# ProPrj___2025-09-13.net
KiCad netlist of a schematic drawn in EasyEDA Pro
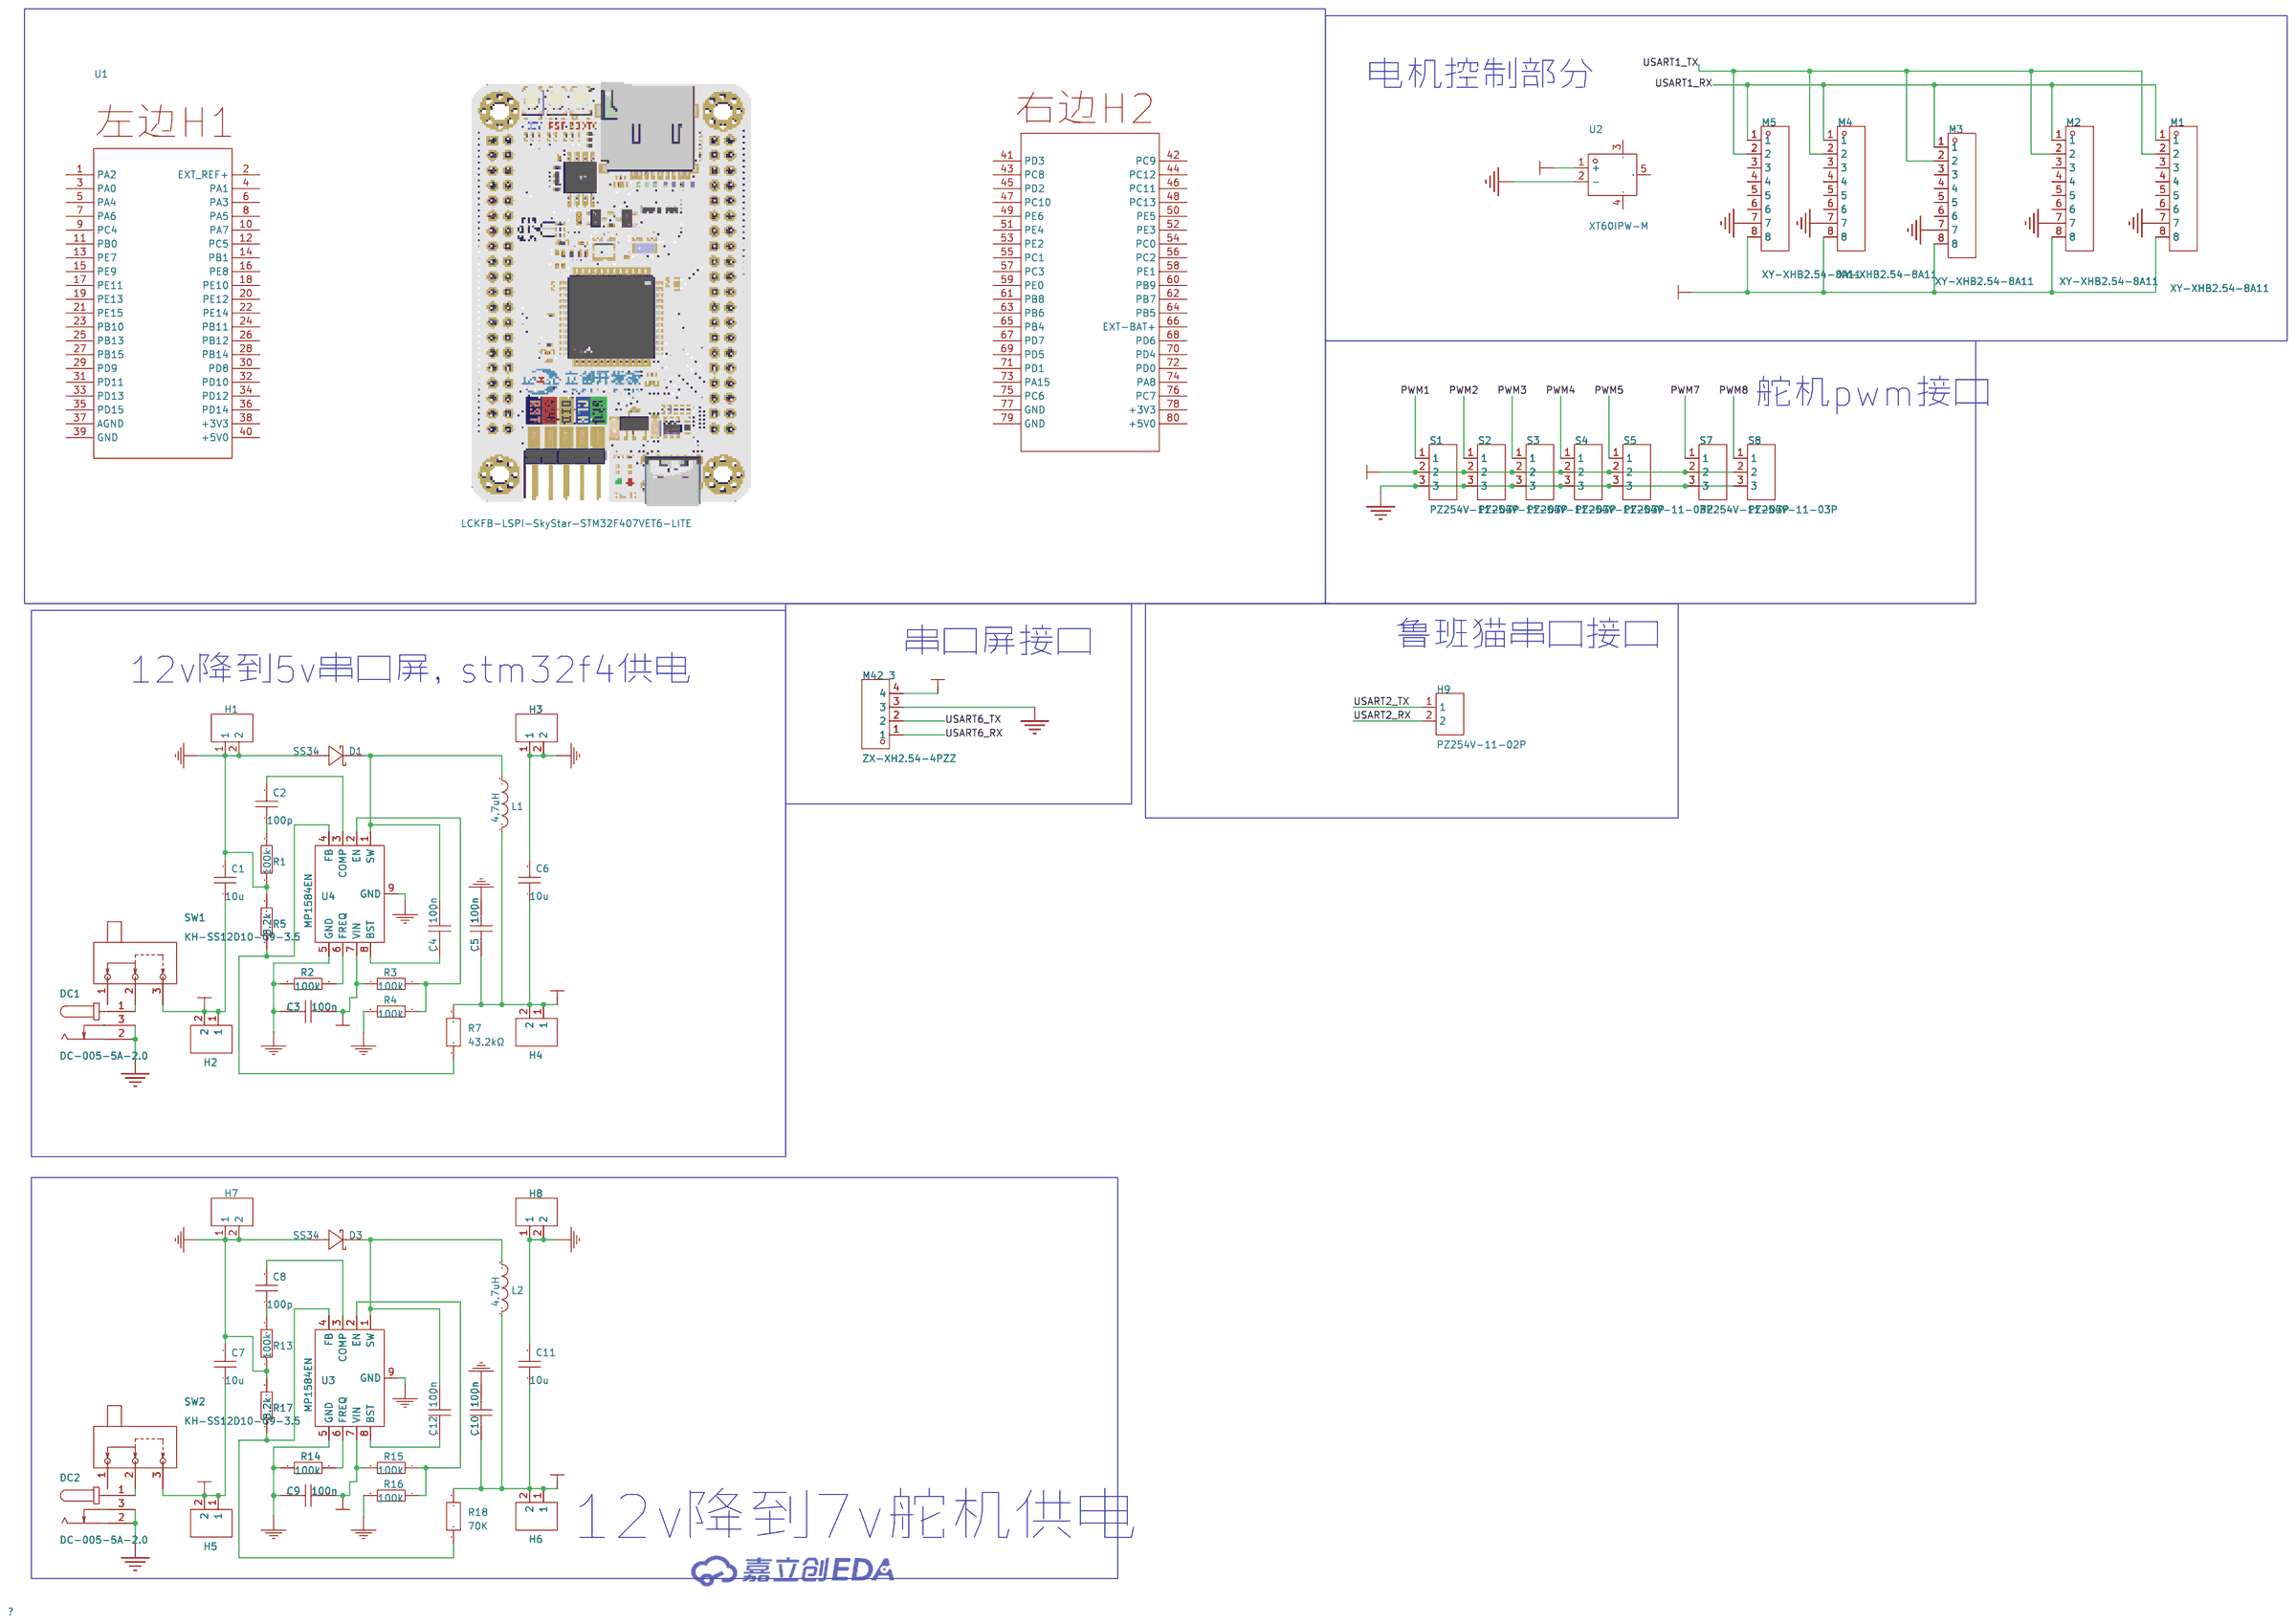
[diagram p0: schematic sheet]

(export (version "E")
  (design (tool "Eeschema 10.0.6"))
  (components
    (comp (ref "C1")
      (value "10u")
      (footprint "easyedapro:C1206")
      (fields (field (name "Manufacturer Part") "CL31A106KBHNNNE") (field (name "Manufacturer") "SAMSUNG"))
      (libsource (lib "easyedapro") (part "10u"))
    )
    (comp (ref "C2")
      (value "100p")
      (footprint "easyedapro:C0603")
      (fields (field (name "Manufacturer Part") "0603CG101J500NT") (field (name "Manufacturer") "FH"))
      (libsource (lib "easyedapro") (part "100p"))
    )
    (comp (ref "C3")
      (value "100n")
      (footprint "easyedapro:C0603")
      (fields (field (name "Manufacturer Part") "CC0603KRX7R9BB104") (field (name "Manufacturer") "YAGEO"))
      (libsource (lib "easyedapro") (part "100n"))
    )
    (comp (ref "C4")
      (value "100n")
      (footprint "easyedapro:C0603")
      (fields (field (name "Manufacturer Part") "CC0603KRX7R9BB104") (field (name "Manufacturer") "YAGEO"))
      (libsource (lib "easyedapro") (part "100n"))
    )
    (comp (ref "C5")
      (value "100n")
      (footprint "easyedapro:C0603")
      (fields (field (name "Manufacturer Part") "CC0603KRX7R9BB104") (field (name "Manufacturer") "YAGEO"))
      (libsource (lib "easyedapro") (part "100n"))
    )
    (comp (ref "C6")
      (value "10u")
      (footprint "easyedapro:C1206")
      (fields (field (name "Manufacturer Part") "CL31A106KBHNNNE") (field (name "Manufacturer") "SAMSUNG"))
      (libsource (lib "easyedapro") (part "10u"))
    )
    (comp (ref "C7")
      (value "10u")
      (footprint "easyedapro:C1206")
      (fields (field (name "Manufacturer Part") "CL31A106KBHNNNE") (field (name "Manufacturer") "SAMSUNG"))
      (libsource (lib "easyedapro") (part "10u"))
    )
    (comp (ref "C8")
      (value "100p")
      (footprint "easyedapro:C0603")
      (fields (field (name "Manufacturer Part") "0603CG101J500NT") (field (name "Manufacturer") "FH"))
      (libsource (lib "easyedapro") (part "100p"))
    )
    (comp (ref "C9")
      (value "100n")
      (footprint "easyedapro:C0603")
      (fields (field (name "Manufacturer Part") "CC0603KRX7R9BB104") (field (name "Manufacturer") "YAGEO"))
      (libsource (lib "easyedapro") (part "100n"))
    )
    (comp (ref "C10")
      (value "100n")
      (footprint "easyedapro:C0603")
      (fields (field (name "Manufacturer Part") "CC0603KRX7R9BB104") (field (name "Manufacturer") "YAGEO"))
      (libsource (lib "easyedapro") (part "100n"))
    )
    (comp (ref "C11")
      (value "10u")
      (footprint "easyedapro:C1206")
      (fields (field (name "Manufacturer Part") "CL31A106KBHNNNE") (field (name "Manufacturer") "SAMSUNG"))
      (libsource (lib "easyedapro") (part "10u"))
    )
    (comp (ref "C12")
      (value "100n")
      (footprint "easyedapro:C0603")
      (fields (field (name "Manufacturer Part") "CC0603KRX7R9BB104") (field (name "Manufacturer") "YAGEO"))
      (libsource (lib "easyedapro") (part "100n"))
    )
    (comp (ref "D1")
      (value "SS34")
      (footprint "easyedapro:SMA_L4.2-W2.7-LS5.0-RD")
      (fields (field (name "Manufacturer") "KUU"))
      (libsource (lib "easyedapro") (part "SS34"))
    )
    (comp (ref "D3")
      (value "SS34")
      (footprint "easyedapro:SMA_L4.2-W2.7-LS5.0-RD")
      (fields (field (name "Manufacturer") "KUU"))
      (libsource (lib "easyedapro") (part "SS34"))
    )
    (comp (ref "DC1")
      (value "DC-005-5A-2.0")
      (footprint "easyedapro:DC-IN-TH_DC-005-5A-2.0")
      (description "连接器类型:DC电源插座;安装方式:弯插;触点内径:2mm;触点外径:6.2mm;额定电流:5A;额定电压:24V;工作温度范围:-20°C~+70°C;")
      (fields (field (name "Manufacturer") "XKB Connection(中国星坤)"))
      (libsource (lib "easyedapro") (part "DC-005-5A-2.0"))
    )
    (comp (ref "DC2")
      (value "DC-005-5A-2.0")
      (footprint "easyedapro:DC-IN-TH_DC-005-5A-2.0")
      (description "连接器类型:DC电源插座;安装方式:弯插;触点内径:2mm;触点外径:6.2mm;额定电流:5A;额定电压:24V;工作温度范围:-20°C~+70°C;")
      (fields (field (name "Manufacturer") "XKB Connection(中国星坤)"))
      (libsource (lib "easyedapro") (part "DC-005-5A-2.0"))
    )
    (comp (ref "H1")
      (value "KH-2.54PH180-1X2P-L11.5")
      (footprint "easyedapro:HDR-TH_2P-P2.54-V-M")
      (fields (field (name "Manufacturer") "kinghelm(金航标)"))
      (libsource (lib "easyedapro") (part "KH-2.54PH180-1X2P-L11.5"))
    )
    (comp (ref "H2")
      (value "KH-2.54PH180-1X2P-L11.5")
      (footprint "easyedapro:HDR-TH_2P-P2.54-V-M")
      (fields (field (name "Manufacturer") "kinghelm(金航标)"))
      (libsource (lib "easyedapro") (part "KH-2.54PH180-1X2P-L11.5"))
    )
    (comp (ref "H3")
      (value "KH-2.54PH180-1X2P-L11.5")
      (footprint "easyedapro:HDR-TH_2P-P2.54-V-M")
      (fields (field (name "Manufacturer") "kinghelm(金航标)"))
      (libsource (lib "easyedapro") (part "KH-2.54PH180-1X2P-L11.5"))
    )
    (comp (ref "H4")
      (value "KH-2.54PH180-1X2P-L11.5")
      (footprint "easyedapro:HDR-TH_2P-P2.54-V-M")
      (fields (field (name "Manufacturer") "kinghelm(金航标)"))
      (libsource (lib "easyedapro") (part "KH-2.54PH180-1X2P-L11.5"))
    )
    (comp (ref "H5")
      (value "KH-2.54PH180-1X2P-L11.5")
      (footprint "easyedapro:HDR-TH_2P-P2.54-V-M")
      (fields (field (name "Manufacturer") "kinghelm(金航标)"))
      (libsource (lib "easyedapro") (part "KH-2.54PH180-1X2P-L11.5"))
    )
    (comp (ref "H6")
      (value "KH-2.54PH180-1X2P-L11.5")
      (footprint "easyedapro:HDR-TH_2P-P2.54-V-M")
      (fields (field (name "Manufacturer") "kinghelm(金航标)"))
      (libsource (lib "easyedapro") (part "KH-2.54PH180-1X2P-L11.5"))
    )
    (comp (ref "H7")
      (value "KH-2.54PH180-1X2P-L11.5")
      (footprint "easyedapro:HDR-TH_2P-P2.54-V-M")
      (fields (field (name "Manufacturer") "kinghelm(金航标)"))
      (libsource (lib "easyedapro") (part "KH-2.54PH180-1X2P-L11.5"))
    )
    (comp (ref "H8")
      (value "KH-2.54PH180-1X2P-L11.5")
      (footprint "easyedapro:HDR-TH_2P-P2.54-V-M")
      (fields (field (name "Manufacturer") "kinghelm(金航标)"))
      (libsource (lib "easyedapro") (part "KH-2.54PH180-1X2P-L11.5"))
    )
    (comp (ref "H9")
      (value "PZ254V-11-02P")
      (footprint "easyedapro:HDR-TH_2P-P2.54-V-M")
      (fields (field (name "Manufacturer") "XFCN(兴飞)"))
      (libsource (lib "easyedapro") (part "PZ254V-11-02P"))
    )
    (comp (ref "L1")
      (value "4.7uH")
      (footprint "easyedapro:IND-SMD_L6.0-W6.0_SLF6028T")
      (fields
        (field (name "Manufacturer Part") "SLO0630H4R7MTT")
        (field (name "Manufacturer") "Sunltech Tech")
      )
      (libsource (lib "easyedapro") (part "4.7uH"))
    )
    (comp (ref "L2")
      (value "4.7uH")
      (footprint "easyedapro:IND-SMD_L6.0-W6.0_SLF6028T")
      (fields
        (field (name "Manufacturer Part") "SLO0630H4R7MTT")
        (field (name "Manufacturer") "Sunltech Tech")
      )
      (libsource (lib "easyedapro") (part "4.7uH"))
    )
    (comp (ref "M1")
      (value "XY-XHB2.54-8A11")
      (fields (field (name "Manufacturer") "XYECONN(辛译)"))
      (libsource (lib "easyedapro") (part "KH-A2504-R-08AWD"))
    )
    (comp (ref "M2")
      (value "XY-XHB2.54-8A11")
      (fields (field (name "Manufacturer") "XYECONN(辛译)"))
      (libsource (lib "easyedapro") (part "KH-A2504-R-08AWD"))
    )
    (comp (ref "M3")
      (value "XY-XHB2.54-8A11")
      (fields (field (name "Manufacturer") "XYECONN(辛译)"))
      (libsource (lib "easyedapro") (part "KH-A2504-R-08AWD"))
    )
    (comp (ref "M4")
      (value "XY-XHB2.54-8A11")
      (fields (field (name "Manufacturer") "XYECONN(辛译)"))
      (libsource (lib "easyedapro") (part "KH-A2504-R-08AWD"))
    )
    (comp (ref "M5")
      (value "XY-XHB2.54-8A11")
      (fields (field (name "Manufacturer") "XYECONN(辛译)"))
      (libsource (lib "easyedapro") (part "KH-A2504-R-08AWD"))
    )
    (comp (ref "M42_3")
      (value "ZX-XH2.54-4PZZ")
      (footprint "easyedapro:CONN-TH_4P-P2.50_4PIN")
      (fields (field (name "Manufacturer") "Megastar(兆星)"))
      (libsource (lib "easyedapro") (part "ZX-XH2.54-4PZZ"))
    )
    (comp (ref "R1")
      (value "100k")
      (footprint "easyedapro:R0603")
      (fields (field (name "Manufacturer Part") "0603WAF1003T5E") (field (name "Manufacturer") "UniOhm"))
      (libsource (lib "easyedapro") (part "100k"))
    )
    (comp (ref "R2")
      (value "100k")
      (footprint "easyedapro:R0603")
      (fields (field (name "Manufacturer Part") "0603WAF1003T5E") (field (name "Manufacturer") "UniOhm"))
      (libsource (lib "easyedapro") (part "100k"))
    )
    (comp (ref "R3")
      (value "100k")
      (footprint "easyedapro:R0603")
      (fields (field (name "Manufacturer Part") "0603WAF1003T5E") (field (name "Manufacturer") "UniOhm"))
      (libsource (lib "easyedapro") (part "100k"))
    )
    (comp (ref "R4")
      (value "100k")
      (footprint "easyedapro:R0603")
      (fields (field (name "Manufacturer Part") "0603WAF1003T5E") (field (name "Manufacturer") "UniOhm"))
      (libsource (lib "easyedapro") (part "100k"))
    )
    (comp (ref "R5")
      (value "8.2k")
      (footprint "easyedapro:R0603")
      (fields (field (name "Manufacturer Part") "0603WAF8201T5E") (field (name "Manufacturer") "UniOhm"))
      (libsource (lib "easyedapro") (part "8.2k"))
    )
    (comp (ref "R7")
      (value "43.2kΩ")
      (footprint "easyedapro:R0603")
      (description "5V_1")
      (fields (field (name "Manufacturer Part") "FRC0603F4322TS") (field (name "Manufacturer") "FOJAN(富捷)"))
      (libsource (lib "easyedapro") (part "FRC0603F4322TS"))
    )
    (comp (ref "R13")
      (value "100k")
      (footprint "easyedapro:R0603")
      (fields (field (name "Manufacturer Part") "0603WAF1003T5E") (field (name "Manufacturer") "UniOhm"))
      (libsource (lib "easyedapro") (part "100k"))
    )
    (comp (ref "R14")
      (value "100k")
      (footprint "easyedapro:R0603")
      (fields (field (name "Manufacturer Part") "0603WAF1003T5E") (field (name "Manufacturer") "UniOhm"))
      (libsource (lib "easyedapro") (part "100k"))
    )
    (comp (ref "R15")
      (value "100k")
      (footprint "easyedapro:R0603")
      (fields (field (name "Manufacturer Part") "0603WAF1003T5E") (field (name "Manufacturer") "UniOhm"))
      (libsource (lib "easyedapro") (part "100k"))
    )
    (comp (ref "R16")
      (value "100k")
      (footprint "easyedapro:R0603")
      (fields (field (name "Manufacturer Part") "0603WAF1003T5E") (field (name "Manufacturer") "UniOhm"))
      (libsource (lib "easyedapro") (part "100k"))
    )
    (comp (ref "R17")
      (value "8.2k")
      (footprint "easyedapro:R0603")
      (fields (field (name "Manufacturer Part") "0603WAF8201T5E") (field (name "Manufacturer") "UniOhm"))
      (libsource (lib "easyedapro") (part "8.2k"))
    )
    (comp (ref "R18")
      (value "70K")
      (footprint "easyedapro:R0603")
      (description "5V_1")
      (fields (field (name "Manufacturer Part") "FRC0603F4322TS") (field (name "Manufacturer") "FOJAN(富捷)"))
      (libsource (lib "easyedapro") (part "FRC0603F4322TS"))
    )
    (comp (ref "S1")
      (value "PZ254V-11-03P")
      (footprint "easyedapro:HDR-TH_3P-P2.54-V-M")
      (fields (field (name "Manufacturer") "XFCN(兴飞)"))
      (libsource (lib "easyedapro") (part "PZ254V-11-03P_C2937625"))
    )
    (comp (ref "S2")
      (value "PZ254V-11-03P")
      (footprint "easyedapro:HDR-TH_3P-P2.54-V-M")
      (fields (field (name "Manufacturer") "XFCN(兴飞)"))
      (libsource (lib "easyedapro") (part "PZ254V-11-03P_C2937625"))
    )
    (comp (ref "S3")
      (value "PZ254V-11-03P")
      (footprint "easyedapro:HDR-TH_3P-P2.54-V-M")
      (fields (field (name "Manufacturer") "XFCN(兴飞)"))
      (libsource (lib "easyedapro") (part "PZ254V-11-03P_C2937625"))
    )
    (comp (ref "S4")
      (value "PZ254V-11-03P")
      (footprint "easyedapro:HDR-TH_3P-P2.54-V-M")
      (fields (field (name "Manufacturer") "XFCN(兴飞)"))
      (libsource (lib "easyedapro") (part "PZ254V-11-03P_C2937625"))
    )
    (comp (ref "S5")
      (value "PZ254V-11-03P")
      (footprint "easyedapro:HDR-TH_3P-P2.54-V-M")
      (fields (field (name "Manufacturer") "XFCN(兴飞)"))
      (libsource (lib "easyedapro") (part "PZ254V-11-03P_C2937625"))
    )
    (comp (ref "S7")
      (value "PZ254V-11-03P")
      (footprint "easyedapro:HDR-TH_3P-P2.54-V-M")
      (fields (field (name "Manufacturer") "XFCN(兴飞)"))
      (libsource (lib "easyedapro") (part "PZ254V-11-03P_C2937625"))
    )
    (comp (ref "S8")
      (value "PZ254V-11-03P")
      (footprint "easyedapro:HDR-TH_3P-P2.54-V-M")
      (fields (field (name "Manufacturer") "XFCN(兴飞)"))
      (libsource (lib "easyedapro") (part "PZ254V-11-03P_C2937625"))
    )
    (comp (ref "SW1")
      (value "KH-SS12D10-G9-3.5")
      (footprint "easyedapro:SW-TH_KH-SS12D10-G9-3.5")
      (fields (field (name "Manufacturer") "kinghelm(金航标)"))
      (libsource (lib "easyedapro") (part "KH-SS12D10-G9-3.5"))
    )
    (comp (ref "SW2")
      (value "KH-SS12D10-G9-3.5")
      (footprint "easyedapro:SW-TH_KH-SS12D10-G9-3.5")
      (fields (field (name "Manufacturer") "kinghelm(金航标)"))
      (libsource (lib "easyedapro") (part "KH-SS12D10-G9-3.5"))
    )
    (comp (ref "U1")
      (value "LCKFB-LSPI-SkyStar-STM32F407VET6-LITE")
      (footprint "easyedapro:COMM-TH_LCKFB-LSPI-SKYSTAR-STM32F407VET6-LITE")
      (fields (field (name "Manufacturer") "立创开发板"))
      (libsource (lib "easyedapro") (part "LCKFB-LSPI-SKYSTAR-STM32F407VET6-LITE"))
    )
    (comp (ref "U2")
      (value "XT60IPW-M")
      (footprint "easyedapro:XT60-TH_XT60IPW-M")
      (libsource (lib "easyedapro") (part "XT60IPW-M"))
    )
    (comp (ref "U3")
      (value "MP1584EN")
      (footprint "easyedapro:SOIC-8_L4.9-W3.9-P1.27-LS6.0-BL-EP3.3")
      (libsource (lib "easyedapro") (part "MP1584EN"))
    )
    (comp (ref "U4")
      (value "MP1584EN")
      (footprint "easyedapro:SOIC-8_L4.9-W3.9-P1.27-LS6.0-BL-EP3.3")
      (libsource (lib "easyedapro") (part "MP1584EN"))
    )
  )
  (nets
    (net (code "1") (name "/PWM1") (class "Default")
      (node (ref "S1") (pin "1") (pinfunction "1_1") (pintype "unspecified"))
    )
    (net (code "2") (name "/PWM2") (class "Default")
      (node (ref "S2") (pin "1") (pinfunction "1_1") (pintype "unspecified"))
    )
    (net (code "3") (name "/PWM3") (class "Default")
      (node (ref "S3") (pin "1") (pinfunction "1_1") (pintype "unspecified"))
    )
    (net (code "4") (name "/PWM4") (class "Default")
      (node (ref "S4") (pin "1") (pinfunction "1_1") (pintype "unspecified"))
    )
    (net (code "5") (name "/PWM5") (class "Default")
      (node (ref "S5") (pin "1") (pinfunction "1_1") (pintype "unspecified"))
    )
    (net (code "6") (name "/PWM7") (class "Default")
      (node (ref "S7") (pin "1") (pinfunction "1_1") (pintype "unspecified"))
    )
    (net (code "7") (name "/PWM8") (class "Default")
      (node (ref "S8") (pin "1") (pinfunction "1_1") (pintype "unspecified"))
    )
    (net (code "8") (name "/USART1_RX") (class "Default")
      (node (ref "M1") (pin "1") (pinfunction "1_1") (pintype "unspecified"))
      (node (ref "M2") (pin "1") (pinfunction "1_1") (pintype "unspecified"))
      (node (ref "M3") (pin "1") (pinfunction "1_1") (pintype "unspecified"))
      (node (ref "M4") (pin "1") (pinfunction "1_1") (pintype "unspecified"))
      (node (ref "M5") (pin "1") (pinfunction "1_1") (pintype "unspecified"))
    )
    (net (code "9") (name "/USART1_TX") (class "Default")
      (node (ref "M1") (pin "2") (pinfunction "2_2") (pintype "unspecified"))
      (node (ref "M2") (pin "2") (pinfunction "2_2") (pintype "unspecified"))
      (node (ref "M3") (pin "2") (pinfunction "2_2") (pintype "unspecified"))
      (node (ref "M4") (pin "2") (pinfunction "2_2") (pintype "unspecified"))
      (node (ref "M5") (pin "2") (pinfunction "2_2") (pintype "unspecified"))
    )
    (net (code "10") (name "/USART2_RX") (class "Default")
      (node (ref "H9") (pin "2") (pinfunction "2_2") (pintype "unspecified"))
    )
    (net (code "11") (name "/USART2_TX") (class "Default")
      (node (ref "H9") (pin "1") (pinfunction "1_1") (pintype "unspecified"))
    )
    (net (code "12") (name "/USART6_RX") (class "Default")
      (node (ref "M42_3") (pin "1") (pinfunction "1_1") (pintype "unspecified"))
    )
    (net (code "13") (name "/USART6_TX") (class "Default")
      (node (ref "M42_3") (pin "2") (pinfunction "2_2") (pintype "unspecified"))
    )
    (net (code "14") (name "5V_1") (class "Default")
      (node (ref "C5") (pin "1") (pinfunction "1_1") (pintype "unspecified"))
      (node (ref "C6") (pin "1") (pinfunction "1_1") (pintype "input"))
      (node (ref "H4") (pin "1") (pinfunction "1_1") (pintype "unspecified"))
      (node (ref "H4") (pin "2") (pinfunction "2_2") (pintype "unspecified"))
      (node (ref "L1") (pin "2") (pinfunction "2_2") (pintype "unspecified"))
      (node (ref "R7") (pin "2") (pinfunction "2_2") (pintype "unspecified"))
    )
    (net (code "15") (name "5V_2") (class "Default")
      (node (ref "M42_3") (pin "4") (pinfunction "4_4") (pintype "unspecified"))
    )
    (net (code "16") (name "7V") (class "Default")
      (node (ref "C10") (pin "1") (pinfunction "1_1") (pintype "unspecified"))
      (node (ref "C11") (pin "1") (pinfunction "1_1") (pintype "input"))
      (node (ref "H6") (pin "1") (pinfunction "1_1") (pintype "unspecified"))
      (node (ref "H6") (pin "2") (pinfunction "2_2") (pintype "unspecified"))
      (node (ref "L2") (pin "2") (pinfunction "2_2") (pintype "unspecified"))
      (node (ref "R18") (pin "2") (pinfunction "2_2") (pintype "unspecified"))
      (node (ref "S1") (pin "2") (pinfunction "2_2") (pintype "unspecified"))
      (node (ref "S2") (pin "2") (pinfunction "2_2") (pintype "unspecified"))
      (node (ref "S3") (pin "2") (pinfunction "2_2") (pintype "unspecified"))
      (node (ref "S4") (pin "2") (pinfunction "2_2") (pintype "unspecified"))
      (node (ref "S5") (pin "2") (pinfunction "2_2") (pintype "unspecified"))
      (node (ref "S7") (pin "2") (pinfunction "2_2") (pintype "unspecified"))
      (node (ref "S8") (pin "2") (pinfunction "2_2") (pintype "unspecified"))
    )
    (net (code "17") (name "12V_1") (class "Default")
      (node (ref "C1") (pin "1") (pinfunction "1_1") (pintype "input"))
      (node (ref "C3") (pin "2") (pinfunction "2_2") (pintype "unspecified"))
      (node (ref "H2") (pin "1") (pinfunction "1_1") (pintype "unspecified"))
      (node (ref "H2") (pin "2") (pinfunction "2_2") (pintype "unspecified"))
      (node (ref "M1") (pin "8") (pinfunction "8_8") (pintype "unspecified"))
      (node (ref "M2") (pin "8") (pinfunction "8_8") (pintype "unspecified"))
      (node (ref "M3") (pin "8") (pinfunction "8_8") (pintype "unspecified"))
      (node (ref "M4") (pin "8") (pinfunction "8_8") (pintype "unspecified"))
      (node (ref "M5") (pin "8") (pinfunction "8_8") (pintype "unspecified"))
      (node (ref "R3") (pin "2") (pinfunction "2_2") (pintype "input"))
      (node (ref "SW1") (pin "3") (pinfunction "3_3") (pintype "unspecified"))
      (node (ref "U2") (pin "1") (pinfunction "+_1") (pintype "unspecified"))
      (node (ref "U4") (pin "7") (pinfunction "VIN_7") (pintype "unspecified"))
    )
    (net (code "18") (name "12V_2") (class "Default")
      (node (ref "C7") (pin "1") (pinfunction "1_1") (pintype "input"))
      (node (ref "C9") (pin "2") (pinfunction "2_2") (pintype "unspecified"))
      (node (ref "H5") (pin "1") (pinfunction "1_1") (pintype "unspecified"))
      (node (ref "H5") (pin "2") (pinfunction "2_2") (pintype "unspecified"))
      (node (ref "R15") (pin "2") (pinfunction "2_2") (pintype "input"))
      (node (ref "SW2") (pin "3") (pinfunction "3_3") (pintype "unspecified"))
      (node (ref "U3") (pin "7") (pinfunction "VIN_7") (pintype "unspecified"))
    )
    (net (code "19") (name "GND") (class "Default")
      (node (ref "C1") (pin "2") (pinfunction "2_2") (pintype "input"))
      (node (ref "C10") (pin "2") (pinfunction "2_2") (pintype "unspecified"))
      (node (ref "C11") (pin "2") (pinfunction "2_2") (pintype "input"))
      (node (ref "C3") (pin "1") (pinfunction "1_1") (pintype "unspecified"))
      (node (ref "C5") (pin "2") (pinfunction "2_2") (pintype "unspecified"))
      (node (ref "C6") (pin "2") (pinfunction "2_2") (pintype "input"))
      (node (ref "C7") (pin "2") (pinfunction "2_2") (pintype "input"))
      (node (ref "C9") (pin "1") (pinfunction "1_1") (pintype "unspecified"))
      (node (ref "D1") (pin "2") (pinfunction "A_2") (pintype "unspecified"))
      (node (ref "D3") (pin "2") (pinfunction "A_2") (pintype "unspecified"))
      (node (ref "DC1") (pin "2") (pinfunction "2_2") (pintype "unspecified"))
      (node (ref "DC1") (pin "3") (pinfunction "3_3") (pintype "unspecified"))
      (node (ref "DC2") (pin "2") (pinfunction "2_2") (pintype "unspecified"))
      (node (ref "DC2") (pin "3") (pinfunction "3_3") (pintype "unspecified"))
      (node (ref "H1") (pin "1") (pinfunction "1_1") (pintype "unspecified"))
      (node (ref "H1") (pin "2") (pinfunction "2_2") (pintype "unspecified"))
      (node (ref "H3") (pin "1") (pinfunction "1_1") (pintype "unspecified"))
      (node (ref "H3") (pin "2") (pinfunction "2_2") (pintype "unspecified"))
      (node (ref "H7") (pin "1") (pinfunction "1_1") (pintype "unspecified"))
      (node (ref "H7") (pin "2") (pinfunction "2_2") (pintype "unspecified"))
      (node (ref "H8") (pin "1") (pinfunction "1_1") (pintype "unspecified"))
      (node (ref "H8") (pin "2") (pinfunction "2_2") (pintype "unspecified"))
      (node (ref "M1") (pin "7") (pinfunction "7_7") (pintype "unspecified"))
      (node (ref "M2") (pin "7") (pinfunction "7_7") (pintype "unspecified"))
      (node (ref "M3") (pin "7") (pinfunction "7_7") (pintype "unspecified"))
      (node (ref "M4") (pin "7") (pinfunction "7_7") (pintype "unspecified"))
      (node (ref "M42_3") (pin "3") (pinfunction "3_3") (pintype "unspecified"))
      (node (ref "M5") (pin "7") (pinfunction "7_7") (pintype "unspecified"))
      (node (ref "R1") (pin "1") (pinfunction "1_1") (pintype "input"))
      (node (ref "R13") (pin "1") (pinfunction "1_1") (pintype "input"))
      (node (ref "R14") (pin "2") (pinfunction "2_2") (pintype "input"))
      (node (ref "R16") (pin "2") (pinfunction "2_2") (pintype "input"))
      (node (ref "R17") (pin "2") (pinfunction "2_2") (pintype "input"))
      (node (ref "R2") (pin "2") (pinfunction "2_2") (pintype "input"))
      (node (ref "R4") (pin "2") (pinfunction "2_2") (pintype "input"))
      (node (ref "R5") (pin "2") (pinfunction "2_2") (pintype "input"))
      (node (ref "S1") (pin "3") (pinfunction "3_3") (pintype "unspecified"))
      (node (ref "S2") (pin "3") (pinfunction "3_3") (pintype "unspecified"))
      (node (ref "S3") (pin "3") (pinfunction "3_3") (pintype "unspecified"))
      (node (ref "S4") (pin "3") (pinfunction "3_3") (pintype "unspecified"))
      (node (ref "S5") (pin "3") (pinfunction "3_3") (pintype "unspecified"))
      (node (ref "S7") (pin "3") (pinfunction "3_3") (pintype "unspecified"))
      (node (ref "S8") (pin "3") (pinfunction "3_3") (pintype "unspecified"))
      (node (ref "U2") (pin "2") (pinfunction "-_2") (pintype "unspecified"))
      (node (ref "U3") (pin "5") (pinfunction "GND_5") (pintype "unspecified"))
      (node (ref "U3") (pin "9") (pinfunction "GND_9") (pintype "unspecified"))
      (node (ref "U4") (pin "5") (pinfunction "GND_5") (pintype "unspecified"))
      (node (ref "U4") (pin "9") (pinfunction "GND_9") (pintype "unspecified"))
    )
    (net (code "20") (name "Net-(C2-Pad1)") (class "Default")
      (node (ref "C2") (pin "1") (pinfunction "1_1") (pintype "input"))
      (node (ref "R1") (pin "2") (pinfunction "2_2") (pintype "input"))
    )
    (net (code "21") (name "Net-(C8-Pad1)") (class "Default")
      (node (ref "C8") (pin "1") (pinfunction "1_1") (pintype "input"))
      (node (ref "R13") (pin "2") (pinfunction "2_2") (pintype "input"))
    )
    (net (code "22") (name "Net-(D1-K)") (class "Default")
      (node (ref "C4") (pin "2") (pinfunction "2_2") (pintype "unspecified"))
      (node (ref "D1") (pin "1") (pinfunction "K_1") (pintype "unspecified"))
      (node (ref "L1") (pin "1") (pinfunction "1_1") (pintype "unspecified"))
      (node (ref "U4") (pin "1") (pinfunction "SW_1") (pintype "unspecified"))
    )
    (net (code "23") (name "Net-(D3-K)") (class "Default")
      (node (ref "C12") (pin "2") (pinfunction "2_2") (pintype "unspecified"))
      (node (ref "D3") (pin "1") (pinfunction "K_1") (pintype "unspecified"))
      (node (ref "L2") (pin "1") (pinfunction "1_1") (pintype "unspecified"))
      (node (ref "U3") (pin "1") (pinfunction "SW_1") (pintype "unspecified"))
    )
    (net (code "24") (name "Net-(DC1-Pad1)") (class "Default")
      (node (ref "DC1") (pin "1") (pinfunction "1_1") (pintype "unspecified"))
      (node (ref "SW1") (pin "2") (pinfunction "2_2") (pintype "unspecified"))
    )
    (net (code "25") (name "Net-(DC2-Pad1)") (class "Default")
      (node (ref "DC2") (pin "1") (pinfunction "1_1") (pintype "unspecified"))
      (node (ref "SW2") (pin "2") (pinfunction "2_2") (pintype "unspecified"))
    )
    (net (code "26") (name "Net-(U3-BST)") (class "Default")
      (node (ref "C12") (pin "1") (pinfunction "1_1") (pintype "unspecified"))
      (node (ref "U3") (pin "8") (pinfunction "BST_8") (pintype "unspecified"))
    )
    (net (code "27") (name "Net-(U3-COMP)") (class "Default")
      (node (ref "C8") (pin "2") (pinfunction "2_2") (pintype "input"))
      (node (ref "U3") (pin "3") (pinfunction "COMP_3") (pintype "unspecified"))
    )
    (net (code "28") (name "Net-(U3-EN)") (class "Default")
      (node (ref "R15") (pin "1") (pinfunction "1_1") (pintype "input"))
      (node (ref "R16") (pin "1") (pinfunction "1_1") (pintype "input"))
      (node (ref "U3") (pin "2") (pinfunction "EN_2") (pintype "unspecified"))
    )
    (net (code "29") (name "Net-(U3-FB)") (class "Default")
      (node (ref "R17") (pin "1") (pinfunction "1_1") (pintype "input"))
      (node (ref "R18") (pin "1") (pinfunction "1_1") (pintype "unspecified"))
      (node (ref "U3") (pin "4") (pinfunction "FB_4") (pintype "unspecified"))
    )
    (net (code "30") (name "Net-(U3-FREQ)") (class "Default")
      (node (ref "R14") (pin "1") (pinfunction "1_1") (pintype "input"))
      (node (ref "U3") (pin "6") (pinfunction "FREQ_6") (pintype "unspecified"))
    )
    (net (code "31") (name "Net-(U4-BST)") (class "Default")
      (node (ref "C4") (pin "1") (pinfunction "1_1") (pintype "unspecified"))
      (node (ref "U4") (pin "8") (pinfunction "BST_8") (pintype "unspecified"))
    )
    (net (code "32") (name "Net-(U4-COMP)") (class "Default")
      (node (ref "C2") (pin "2") (pinfunction "2_2") (pintype "input"))
      (node (ref "U4") (pin "3") (pinfunction "COMP_3") (pintype "unspecified"))
    )
    (net (code "33") (name "Net-(U4-EN)") (class "Default")
      (node (ref "R3") (pin "1") (pinfunction "1_1") (pintype "input"))
      (node (ref "R4") (pin "1") (pinfunction "1_1") (pintype "input"))
      (node (ref "U4") (pin "2") (pinfunction "EN_2") (pintype "unspecified"))
    )
    (net (code "34") (name "Net-(U4-FB)") (class "Default")
      (node (ref "R5") (pin "1") (pinfunction "1_1") (pintype "input"))
      (node (ref "R7") (pin "1") (pinfunction "1_1") (pintype "unspecified"))
      (node (ref "U4") (pin "4") (pinfunction "FB_4") (pintype "unspecified"))
    )
    (net (code "35") (name "Net-(U4-FREQ)") (class "Default")
      (node (ref "R2") (pin "1") (pinfunction "1_1") (pintype "input"))
      (node (ref "U4") (pin "6") (pinfunction "FREQ_6") (pintype "unspecified"))
    )
    (net (code "36") (name "unconnected-(M1-Pad3)") (class "Default")
      (node (ref "M1") (pin "3") (pinfunction "3_3") (pintype "unspecified"))
    )
    (net (code "37") (name "unconnected-(M1-Pad4)") (class "Default")
      (node (ref "M1") (pin "4") (pinfunction "4_4") (pintype "unspecified"))
    )
    (net (code "38") (name "unconnected-(M1-Pad5)") (class "Default")
      (node (ref "M1") (pin "5") (pinfunction "5_5") (pintype "unspecified"))
    )
    (net (code "39") (name "unconnected-(M1-Pad6)") (class "Default")
      (node (ref "M1") (pin "6") (pinfunction "6_6") (pintype "unspecified"))
    )
    (net (code "40") (name "unconnected-(M2-Pad3)") (class "Default")
      (node (ref "M2") (pin "3") (pinfunction "3_3") (pintype "unspecified"))
    )
    (net (code "41") (name "unconnected-(M2-Pad4)") (class "Default")
      (node (ref "M2") (pin "4") (pinfunction "4_4") (pintype "unspecified"))
    )
    (net (code "42") (name "unconnected-(M2-Pad5)") (class "Default")
      (node (ref "M2") (pin "5") (pinfunction "5_5") (pintype "unspecified"))
    )
    (net (code "43") (name "unconnected-(M2-Pad6)") (class "Default")
      (node (ref "M2") (pin "6") (pinfunction "6_6") (pintype "unspecified"))
    )
    (net (code "44") (name "unconnected-(M3-Pad3)") (class "Default")
      (node (ref "M3") (pin "3") (pinfunction "3_3") (pintype "unspecified"))
    )
    (net (code "45") (name "unconnected-(M3-Pad4)") (class "Default")
      (node (ref "M3") (pin "4") (pinfunction "4_4") (pintype "unspecified"))
    )
    (net (code "46") (name "unconnected-(M3-Pad5)") (class "Default")
      (node (ref "M3") (pin "5") (pinfunction "5_5") (pintype "unspecified"))
    )
    (net (code "47") (name "unconnected-(M3-Pad6)") (class "Default")
      (node (ref "M3") (pin "6") (pinfunction "6_6") (pintype "unspecified"))
    )
    (net (code "48") (name "unconnected-(M4-Pad3)") (class "Default")
      (node (ref "M4") (pin "3") (pinfunction "3_3") (pintype "unspecified"))
    )
    (net (code "49") (name "unconnected-(M4-Pad4)") (class "Default")
      (node (ref "M4") (pin "4") (pinfunction "4_4") (pintype "unspecified"))
    )
    (net (code "50") (name "unconnected-(M4-Pad5)") (class "Default")
      (node (ref "M4") (pin "5") (pinfunction "5_5") (pintype "unspecified"))
    )
    (net (code "51") (name "unconnected-(M4-Pad6)") (class "Default")
      (node (ref "M4") (pin "6") (pinfunction "6_6") (pintype "unspecified"))
    )
    (net (code "52") (name "unconnected-(M5-Pad3)") (class "Default")
      (node (ref "M5") (pin "3") (pinfunction "3_3") (pintype "unspecified"))
    )
    (net (code "53") (name "unconnected-(M5-Pad4)") (class "Default")
      (node (ref "M5") (pin "4") (pinfunction "4_4") (pintype "unspecified"))
    )
    (net (code "54") (name "unconnected-(M5-Pad5)") (class "Default")
      (node (ref "M5") (pin "5") (pinfunction "5_5") (pintype "unspecified"))
    )
    (net (code "55") (name "unconnected-(M5-Pad6)") (class "Default")
      (node (ref "M5") (pin "6") (pinfunction "6_6") (pintype "unspecified"))
    )
    (net (code "56") (name "unconnected-(SW1-Pad1)") (class "Default")
      (node (ref "SW1") (pin "1") (pinfunction "1_1") (pintype "unspecified"))
    )
    (net (code "57") (name "unconnected-(SW2-Pad1)") (class "Default")
      (node (ref "SW2") (pin "1") (pinfunction "1_1") (pintype "unspecified"))
    )
    (net (code "58") (name "unconnected-(U1-+3V3-Pad38)") (class "Default")
      (node (ref "U1") (pin "38") (pinfunction "+3V3_38") (pintype "unspecified"))
    )
    (net (code "59") (name "unconnected-(U1-+3V3-Pad78)") (class "Default")
      (node (ref "U1") (pin "78") (pinfunction "+3V3_78") (pintype "unspecified"))
    )
    (net (code "60") (name "unconnected-(U1-+5V0-Pad40)") (class "Default")
      (node (ref "U1") (pin "40") (pinfunction "+5V0_40") (pintype "unspecified"))
    )
    (net (code "61") (name "unconnected-(U1-+5V0-Pad80)") (class "Default")
      (node (ref "U1") (pin "80") (pinfunction "+5V0_80") (pintype "unspecified"))
    )
    (net (code "62") (name "unconnected-(U1-AGND-Pad37)") (class "Default")
      (node (ref "U1") (pin "37") (pinfunction "AGND_37") (pintype "unspecified"))
    )
    (net (code "63") (name "unconnected-(U1-EXT-BAT+-Pad66)") (class "Default")
      (node (ref "U1") (pin "66") (pinfunction "EXT-BAT+_66") (pintype "unspecified"))
    )
    (net (code "64") (name "unconnected-(U1-EXT_REF+-Pad2)") (class "Default")
      (node (ref "U1") (pin "2") (pinfunction "EXT_REF+_2") (pintype "unspecified"))
    )
    (net (code "65") (name "unconnected-(U1-GND-Pad39)") (class "Default")
      (node (ref "U1") (pin "39") (pinfunction "GND_39") (pintype "unspecified"))
    )
    (net (code "66") (name "unconnected-(U1-GND-Pad77)") (class "Default")
      (node (ref "U1") (pin "77") (pinfunction "GND_77") (pintype "unspecified"))
    )
    (net (code "67") (name "unconnected-(U1-GND-Pad79)") (class "Default")
      (node (ref "U1") (pin "79") (pinfunction "GND_79") (pintype "unspecified"))
    )
    (net (code "68") (name "unconnected-(U1-PA0-Pad3)") (class "Default")
      (node (ref "U1") (pin "3") (pinfunction "PA0_3") (pintype "bidirectional"))
    )
    (net (code "69") (name "unconnected-(U1-PA1-Pad4)") (class "Default")
      (node (ref "U1") (pin "4") (pinfunction "PA1_4") (pintype "unspecified"))
    )
    (net (code "70") (name "unconnected-(U1-PA2-Pad1)") (class "Default")
      (node (ref "U1") (pin "1") (pinfunction "PA2_1") (pintype "unspecified"))
    )
    (net (code "71") (name "unconnected-(U1-PA3-Pad6)") (class "Default")
      (node (ref "U1") (pin "6") (pinfunction "PA3_6") (pintype "unspecified"))
    )
    (net (code "72") (name "unconnected-(U1-PA4-Pad5)") (class "Default")
      (node (ref "U1") (pin "5") (pinfunction "PA4_5") (pintype "unspecified"))
    )
    (net (code "73") (name "unconnected-(U1-PA5-Pad8)") (class "Default")
      (node (ref "U1") (pin "8") (pinfunction "PA5_8") (pintype "unspecified"))
    )
    (net (code "74") (name "unconnected-(U1-PA6-Pad7)") (class "Default")
      (node (ref "U1") (pin "7") (pinfunction "PA6_7") (pintype "unspecified"))
    )
    (net (code "75") (name "unconnected-(U1-PA7-Pad10)") (class "Default")
      (node (ref "U1") (pin "10") (pinfunction "PA7_10") (pintype "unspecified"))
    )
    (net (code "76") (name "unconnected-(U1-PA8-Pad74)") (class "Default")
      (node (ref "U1") (pin "74") (pinfunction "PA8_74") (pintype "unspecified"))
    )
    (net (code "77") (name "unconnected-(U1-PA15-Pad73)") (class "Default")
      (node (ref "U1") (pin "73") (pinfunction "PA15_73") (pintype "unspecified"))
    )
    (net (code "78") (name "unconnected-(U1-PB0-Pad11)") (class "Default")
      (node (ref "U1") (pin "11") (pinfunction "PB0_11") (pintype "unspecified"))
    )
    (net (code "79") (name "unconnected-(U1-PB1-Pad14)") (class "Default")
      (node (ref "U1") (pin "14") (pinfunction "PB1_14") (pintype "unspecified"))
    )
    (net (code "80") (name "unconnected-(U1-PB4-Pad65)") (class "Default")
      (node (ref "U1") (pin "65") (pinfunction "PB4_65") (pintype "unspecified"))
    )
    (net (code "81") (name "unconnected-(U1-PB5-Pad64)") (class "Default")
      (node (ref "U1") (pin "64") (pinfunction "PB5_64") (pintype "unspecified"))
    )
    (net (code "82") (name "unconnected-(U1-PB6-Pad63)") (class "Default")
      (node (ref "U1") (pin "63") (pinfunction "PB6_63") (pintype "unspecified"))
    )
    (net (code "83") (name "unconnected-(U1-PB7-Pad62)") (class "Default")
      (node (ref "U1") (pin "62") (pinfunction "PB7_62") (pintype "unspecified"))
    )
    (net (code "84") (name "unconnected-(U1-PB8-Pad61)") (class "Default")
      (node (ref "U1") (pin "61") (pinfunction "PB8_61") (pintype "unspecified"))
    )
    (net (code "85") (name "unconnected-(U1-PB9-Pad60)") (class "Default")
      (node (ref "U1") (pin "60") (pinfunction "PB9_60") (pintype "unspecified"))
    )
    (net (code "86") (name "unconnected-(U1-PB10-Pad23)") (class "Default")
      (node (ref "U1") (pin "23") (pinfunction "PB10_23") (pintype "unspecified"))
    )
    (net (code "87") (name "unconnected-(U1-PB11-Pad24)") (class "Default")
      (node (ref "U1") (pin "24") (pinfunction "PB11_24") (pintype "unspecified"))
    )
    (net (code "88") (name "unconnected-(U1-PB12-Pad26)") (class "Default")
      (node (ref "U1") (pin "26") (pinfunction "PB12_26") (pintype "unspecified"))
    )
    (net (code "89") (name "unconnected-(U1-PB13-Pad25)") (class "Default")
      (node (ref "U1") (pin "25") (pinfunction "PB13_25") (pintype "unspecified"))
    )
    (net (code "90") (name "unconnected-(U1-PB14-Pad28)") (class "Default")
      (node (ref "U1") (pin "28") (pinfunction "PB14_28") (pintype "unspecified"))
    )
    (net (code "91") (name "unconnected-(U1-PB15-Pad27)") (class "Default")
      (node (ref "U1") (pin "27") (pinfunction "PB15_27") (pintype "unspecified"))
    )
    (net (code "92") (name "unconnected-(U1-PC0-Pad54)") (class "Default")
      (node (ref "U1") (pin "54") (pinfunction "PC0_54") (pintype "unspecified"))
    )
    (net (code "93") (name "unconnected-(U1-PC1-Pad55)") (class "Default")
      (node (ref "U1") (pin "55") (pinfunction "PC1_55") (pintype "unspecified"))
    )
    (net (code "94") (name "unconnected-(U1-PC2-Pad56)") (class "Default")
      (node (ref "U1") (pin "56") (pinfunction "PC2_56") (pintype "unspecified"))
    )
    (net (code "95") (name "unconnected-(U1-PC3-Pad57)") (class "Default")
      (node (ref "U1") (pin "57") (pinfunction "PC3_57") (pintype "unspecified"))
    )
    (net (code "96") (name "unconnected-(U1-PC4-Pad9)") (class "Default")
      (node (ref "U1") (pin "9") (pinfunction "PC4_9") (pintype "unspecified"))
    )
    (net (code "97") (name "unconnected-(U1-PC5-Pad12)") (class "Default")
      (node (ref "U1") (pin "12") (pinfunction "PC5_12") (pintype "unspecified"))
    )
    (net (code "98") (name "unconnected-(U1-PC6-Pad75)") (class "Default")
      (node (ref "U1") (pin "75") (pinfunction "PC6_75") (pintype "unspecified"))
    )
    (net (code "99") (name "unconnected-(U1-PC7-Pad76)") (class "Default")
      (node (ref "U1") (pin "76") (pinfunction "PC7_76") (pintype "unspecified"))
    )
    (net (code "100") (name "unconnected-(U1-PC8-Pad43)") (class "Default")
      (node (ref "U1") (pin "43") (pinfunction "PC8_43") (pintype "unspecified"))
    )
    (net (code "101") (name "unconnected-(U1-PC9-Pad42)") (class "Default")
      (node (ref "U1") (pin "42") (pinfunction "PC9_42") (pintype "unspecified"))
    )
    (net (code "102") (name "unconnected-(U1-PC10-Pad47)") (class "Default")
      (node (ref "U1") (pin "47") (pinfunction "PC10_47") (pintype "unspecified"))
    )
    (net (code "103") (name "unconnected-(U1-PC11-Pad46)") (class "Default")
      (node (ref "U1") (pin "46") (pinfunction "PC11_46") (pintype "unspecified"))
    )
    (net (code "104") (name "unconnected-(U1-PC12-Pad44)") (class "Default")
      (node (ref "U1") (pin "44") (pinfunction "PC12_44") (pintype "unspecified"))
    )
    (net (code "105") (name "unconnected-(U1-PC13-Pad48)") (class "Default")
      (node (ref "U1") (pin "48") (pinfunction "PC13_48") (pintype "unspecified"))
    )
    (net (code "106") (name "unconnected-(U1-PD0-Pad72)") (class "Default")
      (node (ref "U1") (pin "72") (pinfunction "PD0_72") (pintype "unspecified"))
    )
    (net (code "107") (name "unconnected-(U1-PD1-Pad71)") (class "Default")
      (node (ref "U1") (pin "71") (pinfunction "PD1_71") (pintype "unspecified"))
    )
    (net (code "108") (name "unconnected-(U1-PD2-Pad45)") (class "Default")
      (node (ref "U1") (pin "45") (pinfunction "PD2_45") (pintype "unspecified"))
    )
    (net (code "109") (name "unconnected-(U1-PD3-Pad41)") (class "Default")
      (node (ref "U1") (pin "41") (pinfunction "PD3_41") (pintype "unspecified"))
    )
    (net (code "110") (name "unconnected-(U1-PD4-Pad70)") (class "Default")
      (node (ref "U1") (pin "70") (pinfunction "PD4_70") (pintype "unspecified"))
    )
    (net (code "111") (name "unconnected-(U1-PD5-Pad69)") (class "Default")
      (node (ref "U1") (pin "69") (pinfunction "PD5_69") (pintype "unspecified"))
    )
    (net (code "112") (name "unconnected-(U1-PD6-Pad68)") (class "Default")
      (node (ref "U1") (pin "68") (pinfunction "PD6_68") (pintype "unspecified"))
    )
    (net (code "113") (name "unconnected-(U1-PD7-Pad67)") (class "Default")
      (node (ref "U1") (pin "67") (pinfunction "PD7_67") (pintype "unspecified"))
    )
    (net (code "114") (name "unconnected-(U1-PD8-Pad30)") (class "Default")
      (node (ref "U1") (pin "30") (pinfunction "PD8_30") (pintype "unspecified"))
    )
    (net (code "115") (name "unconnected-(U1-PD9-Pad29)") (class "Default")
      (node (ref "U1") (pin "29") (pinfunction "PD9_29") (pintype "unspecified"))
    )
    (net (code "116") (name "unconnected-(U1-PD10-Pad32)") (class "Default")
      (node (ref "U1") (pin "32") (pinfunction "PD10_32") (pintype "unspecified"))
    )
    (net (code "117") (name "unconnected-(U1-PD11-Pad31)") (class "Default")
      (node (ref "U1") (pin "31") (pinfunction "PD11_31") (pintype "unspecified"))
    )
    (net (code "118") (name "unconnected-(U1-PD12-Pad34)") (class "Default")
      (node (ref "U1") (pin "34") (pinfunction "PD12_34") (pintype "unspecified"))
    )
    (net (code "119") (name "unconnected-(U1-PD13-Pad33)") (class "Default")
      (node (ref "U1") (pin "33") (pinfunction "PD13_33") (pintype "unspecified"))
    )
    (net (code "120") (name "unconnected-(U1-PD14-Pad36)") (class "Default")
      (node (ref "U1") (pin "36") (pinfunction "PD14_36") (pintype "unspecified"))
    )
    (net (code "121") (name "unconnected-(U1-PD15-Pad35)") (class "Default")
      (node (ref "U1") (pin "35") (pinfunction "PD15_35") (pintype "unspecified"))
    )
    (net (code "122") (name "unconnected-(U1-PE0-Pad59)") (class "Default")
      (node (ref "U1") (pin "59") (pinfunction "PE0_59") (pintype "unspecified"))
    )
    (net (code "123") (name "unconnected-(U1-PE1-Pad58)") (class "Default")
      (node (ref "U1") (pin "58") (pinfunction "PE1_58") (pintype "unspecified"))
    )
    (net (code "124") (name "unconnected-(U1-PE2-Pad53)") (class "Default")
      (node (ref "U1") (pin "53") (pinfunction "PE2_53") (pintype "unspecified"))
    )
    (net (code "125") (name "unconnected-(U1-PE3-Pad52)") (class "Default")
      (node (ref "U1") (pin "52") (pinfunction "PE3_52") (pintype "unspecified"))
    )
    (net (code "126") (name "unconnected-(U1-PE4-Pad51)") (class "Default")
      (node (ref "U1") (pin "51") (pinfunction "PE4_51") (pintype "unspecified"))
    )
    (net (code "127") (name "unconnected-(U1-PE5-Pad50)") (class "Default")
      (node (ref "U1") (pin "50") (pinfunction "PE5_50") (pintype "unspecified"))
    )
    (net (code "128") (name "unconnected-(U1-PE6-Pad49)") (class "Default")
      (node (ref "U1") (pin "49") (pinfunction "PE6_49") (pintype "unspecified"))
    )
    (net (code "129") (name "unconnected-(U1-PE7-Pad13)") (class "Default")
      (node (ref "U1") (pin "13") (pinfunction "PE7_13") (pintype "unspecified"))
    )
    (net (code "130") (name "unconnected-(U1-PE8-Pad16)") (class "Default")
      (node (ref "U1") (pin "16") (pinfunction "PE8_16") (pintype "unspecified"))
    )
    (net (code "131") (name "unconnected-(U1-PE9-Pad15)") (class "Default")
      (node (ref "U1") (pin "15") (pinfunction "PE9_15") (pintype "unspecified"))
    )
    (net (code "132") (name "unconnected-(U1-PE10-Pad18)") (class "Default")
      (node (ref "U1") (pin "18") (pinfunction "PE10_18") (pintype "unspecified"))
    )
    (net (code "133") (name "unconnected-(U1-PE11-Pad17)") (class "Default")
      (node (ref "U1") (pin "17") (pinfunction "PE11_17") (pintype "unspecified"))
    )
    (net (code "134") (name "unconnected-(U1-PE12-Pad20)") (class "Default")
      (node (ref "U1") (pin "20") (pinfunction "PE12_20") (pintype "unspecified"))
    )
    (net (code "135") (name "unconnected-(U1-PE13-Pad19)") (class "Default")
      (node (ref "U1") (pin "19") (pinfunction "PE13_19") (pintype "unspecified"))
    )
    (net (code "136") (name "unconnected-(U1-PE14-Pad22)") (class "Default")
      (node (ref "U1") (pin "22") (pinfunction "PE14_22") (pintype "unspecified"))
    )
    (net (code "137") (name "unconnected-(U1-PE15-Pad21)") (class "Default")
      (node (ref "U1") (pin "21") (pinfunction "PE15_21") (pintype "unspecified"))
    )
    (net (code "138") (name "unconnected-(U2-NC-Pad3)") (class "Default")
      (node (ref "U2") (pin "3") (pinfunction "NC_3") (pintype "unspecified"))
    )
    (net (code "139") (name "unconnected-(U2-NC-Pad4)") (class "Default")
      (node (ref "U2") (pin "4") (pinfunction "NC_4") (pintype "unspecified"))
    )
    (net (code "140") (name "unconnected-(U2-NC-Pad5)") (class "Default")
      (node (ref "U2") (pin "5") (pinfunction "NC_5") (pintype "unspecified"))
    )
  )
)
